# I2C_Step_12V_Ann.net
KiCad netlist of a schematic drawn in Altium Designer
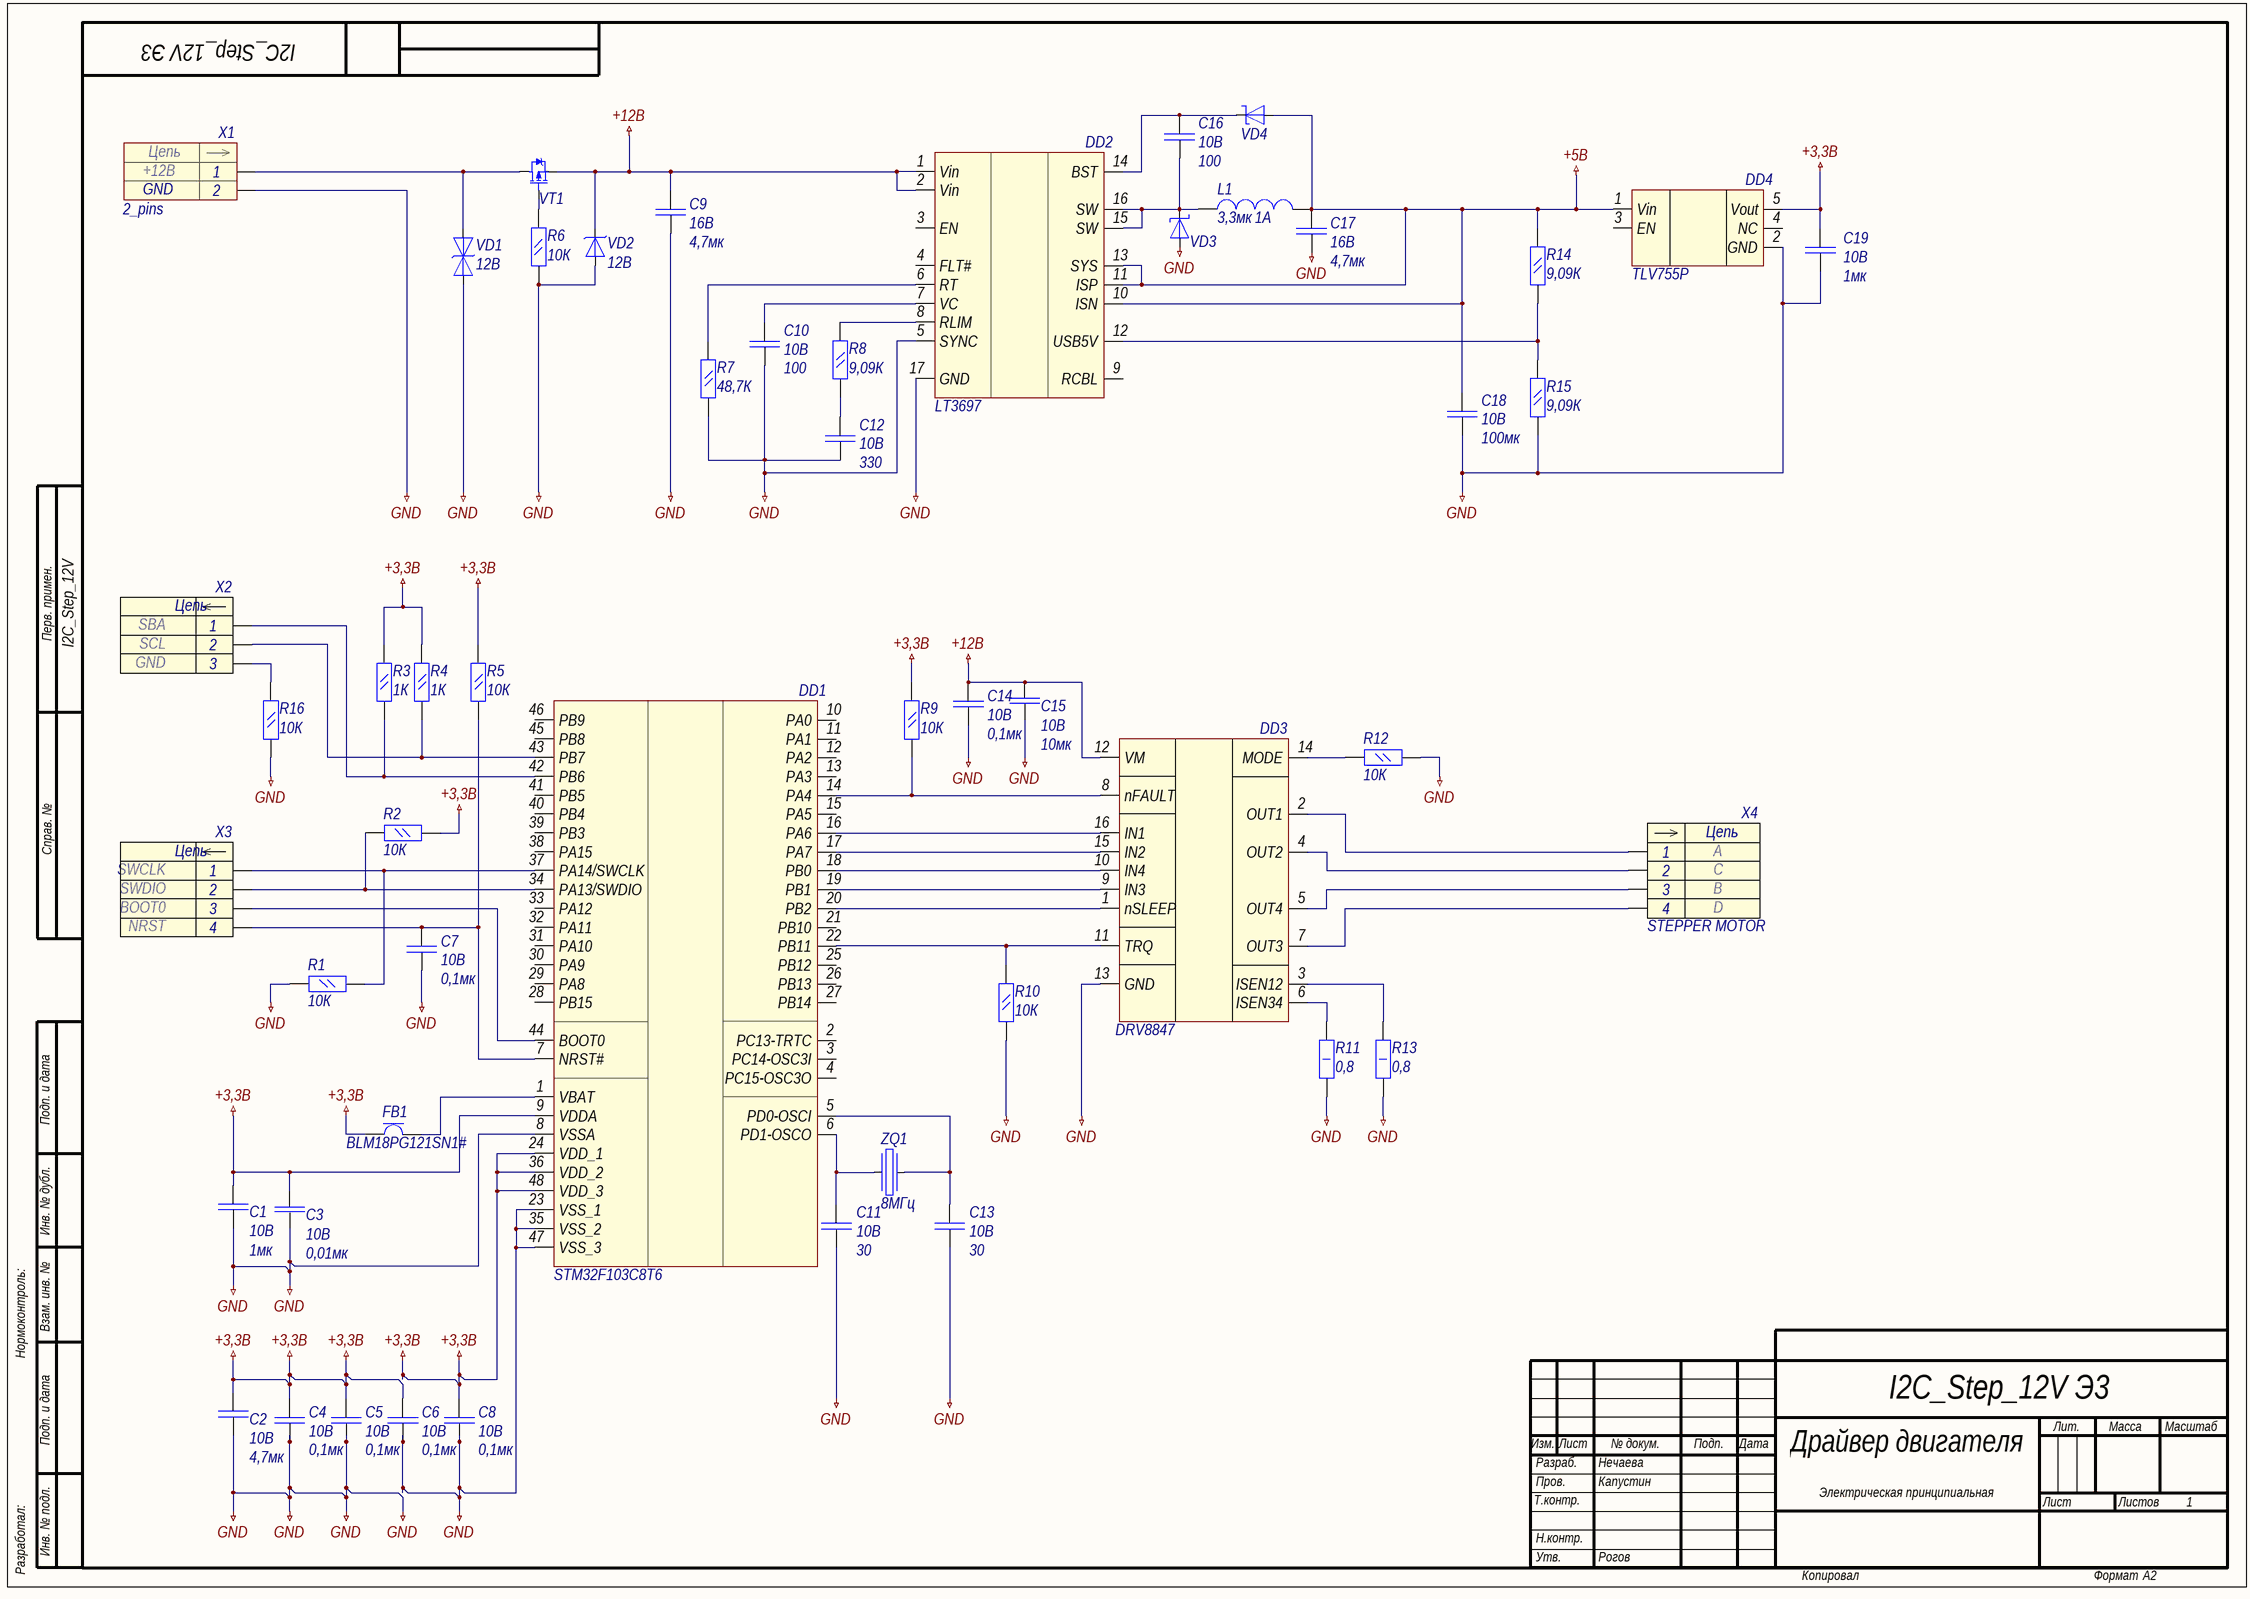
[diagram p0: I2C_Step_12V_Ann.SchDoc]

(export (version "E")
  (design (tool "Eeschema 10.0.6"))
  (components
    (comp (ref "C1")
      (value "Capacitor")
      (footprint "CH0201C")
      (fields (field (name "VOLTAGE") "10В") (field (name "CAPACITANCE") "1мк"))
      (libsource (lib "") (part "Capacitor_1"))
    )
    (comp (ref "C2")
      (value "Capacitor")
      (footprint "CH0402C")
      (fields (field (name "VOLTAGE") "10В") (field (name "CAPACITANCE") "4,7мк"))
      (libsource (lib "") (part "Capacitor_1"))
    )
    (comp (ref "C3")
      (value "Capacitor")
      (footprint "CH0402C")
      (fields (field (name "VOLTAGE") "10В") (field (name "CAPACITANCE") "0,01мк"))
      (libsource (lib "GOST_Capacitors") (part "Capacitor"))
    )
    (comp (ref "C4")
      (value "Capacitor")
      (footprint "CH0402C")
      (fields (field (name "VOLTAGE") "10В") (field (name "CAPACITANCE") "0,1мк"))
      (libsource (lib "") (part "Capacitor_1"))
    )
    (comp (ref "C5")
      (value "Capacitor")
      (footprint "CH0402C")
      (fields (field (name "VOLTAGE") "10В") (field (name "CAPACITANCE") "0,1мк"))
      (libsource (lib "") (part "Capacitor_1"))
    )
    (comp (ref "C6")
      (value "Capacitor")
      (footprint "CH0402C")
      (fields (field (name "VOLTAGE") "10В") (field (name "CAPACITANCE") "0,1мк"))
      (libsource (lib "") (part "Capacitor_1"))
    )
    (comp (ref "C7")
      (value "Capacitor")
      (footprint "CH0402C")
      (fields (field (name "VOLTAGE") "10В") (field (name "CAPACITANCE") "0,1мк"))
      (libsource (lib "") (part "Capacitor_1"))
    )
    (comp (ref "C8")
      (value "Capacitor")
      (footprint "CH0402C")
      (fields (field (name "VOLTAGE") "10В") (field (name "CAPACITANCE") "0,1мк"))
      (libsource (lib "") (part "Capacitor_1"))
    )
    (comp (ref "C9")
      (value "Capacitor")
      (footprint "CH0603C")
      (fields (field (name "VOLTAGE") "16В") (field (name "CAPACITANCE") "4,7мк"))
      (libsource (lib "") (part "Capacitor_1"))
    )
    (comp (ref "C10")
      (value "Capacitor")
      (footprint "CH0201C")
      (fields (field (name "VOLTAGE") "10В") (field (name "CAPACITANCE") "100"))
      (libsource (lib "") (part "Capacitor_1"))
    )
    (comp (ref "C11")
      (value "Capacitor")
      (footprint "CH0201C")
      (fields (field (name "VOLTAGE") "10В") (field (name "CAPACITANCE") "30"))
      (libsource (lib "") (part "Capacitor_1"))
    )
    (comp (ref "C12")
      (value "Capacitor")
      (footprint "CH0402C")
      (fields (field (name "VOLTAGE") "10В") (field (name "CAPACITANCE") "330"))
      (libsource (lib "") (part "Capacitor_1"))
    )
    (comp (ref "C13")
      (value "Capacitor")
      (footprint "CH0201C")
      (fields (field (name "VOLTAGE") "10В") (field (name "CAPACITANCE") "30"))
      (libsource (lib "") (part "Capacitor_1"))
    )
    (comp (ref "C14")
      (value "Capacitor")
      (footprint "CH0402C")
      (fields (field (name "VOLTAGE") "10В") (field (name "CAPACITANCE") "0,1мк"))
      (libsource (lib "") (part "Capacitor_1"))
    )
    (comp (ref "C15")
      (value "Capacitor")
      (footprint "CH0402C")
      (fields (field (name "VOLTAGE") "10В") (field (name "CAPACITANCE") "10мк"))
      (libsource (lib "GOST_Capacitors") (part "Capacitor"))
    )
    (comp (ref "C16")
      (value "Capacitor")
      (footprint "CH0201C")
      (fields (field (name "VOLTAGE") "10В") (field (name "CAPACITANCE") "100"))
      (libsource (lib "") (part "Capacitor_1"))
    )
    (comp (ref "C17")
      (value "Capacitor")
      (footprint "CH0603C")
      (fields (field (name "VOLTAGE") "16В") (field (name "CAPACITANCE") "4,7мк"))
      (libsource (lib "") (part "Capacitor_1"))
    )
    (comp (ref "C18")
      (value "Capacitor")
      (footprint "CH1206C")
      (fields (field (name "VOLTAGE") "10В") (field (name "CAPACITANCE") "100мк"))
      (libsource (lib "") (part "Capacitor_1"))
    )
    (comp (ref "C19")
      (value "Capacitor")
      (footprint "CH0201C")
      (fields (field (name "VOLTAGE") "10В") (field (name "CAPACITANCE") "1мк"))
      (libsource (lib "") (part "Capacitor_1"))
    )
    (comp (ref "DD1")
      (value "STM32F103C8T6")
      (footprint "STM32F103 48pins")
      (libsource (lib "GOST_lib_devices") (part "STM32"))
    )
    (comp (ref "DD2")
      (value "LT3697")
      (footprint "LT3697")
      (description "6~18 to 5")
      (libsource (lib "GOST_lib_devices") (part "LT3697"))
    )
    (comp (ref "DD3")
      (value "DRV8847")
      (footprint "DRV8847")
      (libsource (lib "GOST_lib_devices") (part "DRV8847"))
    )
    (comp (ref "DD4")
      (value "TLV755P")
      (footprint "SOT23-5")
      (libsource (lib "GOST_lib_devices") (part "LDO +3.3V"))
    )
    (comp (ref "FB1")
      (value "Ferrite bead")
      (footprint "CH0603L")
      (fields (field (name "MODEL") "BLM18PG121SN1#"))
      (libsource (lib "GOST_Inductors") (part "Ferrite bead"))
    )
    (comp (ref "L1")
      (value "*")
      (footprint "CH0805L")
      (fields (field (name "MAX CURRENT") "1А") (field (name "INDUCTANCE") "3,3мк"))
      (libsource (lib "GOST_Inductors") (part "Inductor"))
    )
    (comp (ref "R1")
      (value "Res_0.125")
      (footprint "CH0402R")
      (fields (field (name "IMPEDANCE") "10К"))
      (libsource (lib "GOST_Resistors") (part "Res_0.125"))
    )
    (comp (ref "R2")
      (value "Res_0.125")
      (footprint "CH0402R")
      (fields (field (name "IMPEDANCE") "10К"))
      (libsource (lib "GOST_Resistors") (part "Res_0.125"))
    )
    (comp (ref "R3")
      (value "Res_0.125")
      (footprint "CH0402R")
      (fields (field (name "IMPEDANCE") "1К"))
      (libsource (lib "GOST_Resistors") (part "Res_0.125"))
    )
    (comp (ref "R4")
      (value "Res_0.125")
      (footprint "CH0402R")
      (fields (field (name "IMPEDANCE") "1К"))
      (libsource (lib "GOST_Resistors") (part "Res_0.125"))
    )
    (comp (ref "R5")
      (value "Res_0.125")
      (footprint "CH0402R")
      (fields (field (name "IMPEDANCE") "10К"))
      (libsource (lib "GOST_Resistors") (part "Res_0.125"))
    )
    (comp (ref "R6")
      (value "Res_0.125")
      (footprint "CH0402R")
      (fields (field (name "IMPEDANCE") "10К"))
      (libsource (lib "GOST_Resistors") (part "Res_0.125"))
    )
    (comp (ref "R7")
      (value "Res_0.125")
      (footprint "CH0805R")
      (fields (field (name "IMPEDANCE") "48,7К"))
      (libsource (lib "GOST_Resistors") (part "Res_0.125"))
    )
    (comp (ref "R8")
      (value "Res_0.125")
      (footprint "CH0805R")
      (fields (field (name "IMPEDANCE") "9,09К"))
      (libsource (lib "GOST_Resistors") (part "Res_0.125"))
    )
    (comp (ref "R9")
      (value "Res_0.125")
      (footprint "CH0402R")
      (fields (field (name "IMPEDANCE") "10К"))
      (libsource (lib "GOST_Resistors") (part "Res_0.125"))
    )
    (comp (ref "R10")
      (value "Res_0.125")
      (footprint "CH0402R")
      (fields (field (name "IMPEDANCE") "10К"))
      (libsource (lib "GOST_Resistors") (part "Res_0.125"))
    )
    (comp (ref "R11")
      (value "Res_1")
      (footprint "CH2010R")
      (fields (field (name "POWER") "1Вт") (field (name "IMPEDANCE") "0,8"))
      (libsource (lib "GOST_Resistors") (part "Res_1"))
    )
    (comp (ref "R12")
      (value "Res_0.125")
      (footprint "CH0402R")
      (fields (field (name "IMPEDANCE") "10К"))
      (libsource (lib "GOST_Resistors") (part "Res_0.125"))
    )
    (comp (ref "R13")
      (value "Res_1")
      (footprint "CH2010R")
      (fields (field (name "POWER") "1Вт") (field (name "IMPEDANCE") "0,8"))
      (libsource (lib "GOST_Resistors") (part "Res_1"))
    )
    (comp (ref "R14")
      (value "Res_0.125")
      (footprint "CH0805R")
      (fields (field (name "IMPEDANCE") "9,09К"))
      (libsource (lib "GOST_Resistors") (part "Res_0.125"))
    )
    (comp (ref "R15")
      (value "Res_0.125")
      (footprint "CH0805R")
      (fields (field (name "IMPEDANCE") "9,09К"))
      (libsource (lib "GOST_Resistors") (part "Res_0.125"))
    )
    (comp (ref "R16")
      (value "Res_0.125")
      (footprint "CH0402R")
      (fields (field (name "IMPEDANCE") "10К"))
      (libsource (lib "GOST_Resistors") (part "Res_0.125"))
    )
    (comp (ref "VD1")
      (value "TVS-diod_simmetrical")
      (footprint "CH0201L")
      (fields (field (name "MANUFACTURER") "Littelfuse") (field (name "CLAMPING VOLTAGE") "12В"))
      (libsource (lib "GOST_Diodes") (part "TVS-diod_simmetrical"))
    )
    (comp (ref "VD2")
      (value "TVS-diod_directed")
      (footprint "DO214AA")
      (fields (field (name "MANUFACTURER") "Bourns") (field (name "CLAMPING_VOLTAGE") "12В"))
      (libsource (lib "GOST_Diodes") (part "TVS-diod_directed"))
    )
    (comp (ref "VD3")
      (value "Diod Schottky")
      (footprint "DO214AA")
      (fields (field (name "MANUFACTURER") "Rectron"))
      (libsource (lib "GOST_Diodes") (part "Diod Schottky"))
    )
    (comp (ref "VD4")
      (value "Diod Schottky")
      (footprint "SOT23_132")
      (fields (field (name "MANUFACTURER") "Toshiba"))
      (libsource (lib "GOST_Diodes") (part "Diod Schottky"))
    )
    (comp (ref "VT1")
      (value "*")
      (footprint "SOT23_132")
      (libsource (lib "GOST_Transistors") (part "P-Channel"))
    )
    (comp (ref "X1")
      (value "2_pins")
      (footprint "CON: 163-179PH-EX")
      (fields (field (name "VCC") "+12В"))
      (libsource (lib "GOST_lib_connectors") (part "2_pins"))
    )
    (comp (ref "X2")
      (value "3_pins")
      (footprint "CON: PBS-3")
      (fields (field (name "2") "SCL") (field (name "3") "GND") (field (name "1") "SBA"))
      (libsource (lib "GOST_lib_connectors") (part "3_pins"))
    )
    (comp (ref "X3")
      (value "4_pins")
      (footprint "CON: CWF-4R")
      (fields
        (field (name "2") "SWDIO")
        (field (name "3") "BOOT0")
        (field (name "1") "SWCLK")
        (field (name "4") "NRST")
      )
      (libsource (lib "") (part "4_pins_1"))
    )
    (comp (ref "X4")
      (value "STEPPER MOTOR")
      (footprint "CON: CWF-4R")
      (description "Bipolar Stepper Motor 200 Step 0.35A 12VDC")
      (fields (field (name "2") "C") (field (name "3") "B") (field (name "1") "A") (field (name "4") "D"))
      (libsource (lib "GOST_lib_connectors") (part "4_pins"))
    )
    (comp (ref "ZQ1")
      (value "Oscillator")
      (footprint "OSC: 5032")
      (fields (field (name "FREQ") "8МГц"))
      (libsource (lib "GOST_Miscelanuious") (part "Oscillator"))
    )
  )
  (nets
    (net (code "1") (name "+3,3В") (class "Default")
      (node (ref "C1") (pin "2") (pinfunction "C1-_2") (pintype "power_in"))
      (node (ref "C19") (pin "1") (pinfunction "C1+_1") (pintype "power_in"))
      (node (ref "C2") (pin "2") (pinfunction "C1-_2") (pintype "power_in"))
      (node (ref "C3") (pin "1") (pinfunction "С+_1") (pintype "power_in"))
      (node (ref "C4") (pin "1") (pinfunction "C1+_1") (pintype "power_in"))
      (node (ref "C5") (pin "1") (pinfunction "C1+_1") (pintype "power_in"))
      (node (ref "C6") (pin "1") (pinfunction "C1+_1") (pintype "power_in"))
      (node (ref "C8") (pin "1") (pinfunction "C1+_1") (pintype "power_in"))
      (node (ref "DD1") (pin "24") (pinfunction "VDD_1_24") (pintype "passive"))
      (node (ref "DD1") (pin "36") (pinfunction "VDD_2_36") (pintype "passive"))
      (node (ref "DD1") (pin "48") (pinfunction "VDD_3_48") (pintype "passive"))
      (node (ref "DD1") (pin "9") (pinfunction "VDDA_9") (pintype "passive"))
      (node (ref "DD4") (pin "5") (pinfunction "Vout_5") (pintype "power_in"))
      (node (ref "FB1") (pin "1") (pintype "power_in"))
      (node (ref "R2") (pin "1") (pinfunction "C1-_1") (pintype "power_in"))
      (node (ref "R3") (pin "1") (pinfunction "C1-_1") (pintype "power_in"))
      (node (ref "R4") (pin "1") (pinfunction "C1-_1") (pintype "power_in"))
      (node (ref "R5") (pin "1") (pinfunction "C1-_1") (pintype "power_in"))
      (node (ref "R9") (pin "1") (pinfunction "C1-_1") (pintype "power_in"))
    )
    (net (code "2") (name "+5В") (class "Default")
      (node (ref "C17") (pin "1") (pinfunction "C1+_1") (pintype "power_in"))
      (node (ref "C18") (pin "1") (pinfunction "C1+_1") (pintype "power_in"))
      (node (ref "DD2") (pin "10") (pinfunction "ISN_10") (pintype "power_in"))
      (node (ref "DD2") (pin "11") (pinfunction "ISP_11") (pintype "power_in"))
      (node (ref "DD2") (pin "13") (pinfunction "SYS_13") (pintype "power_in"))
      (node (ref "DD4") (pin "1") (pinfunction "Vin_1") (pintype "power_in"))
      (node (ref "L1") (pin "2") (pinfunction "14_2") (pintype "power_in"))
      (node (ref "R14") (pin "1") (pinfunction "C1-_1") (pintype "power_in"))
      (node (ref "VD4") (pin "1") (pinfunction "1_1") (pintype "passive"))
    )
    (net (code "3") (name "+12В") (class "Default")
      (node (ref "C14") (pin "1") (pinfunction "C1+_1") (pintype "power_in"))
      (node (ref "C15") (pin "1") (pinfunction "С+_1") (pintype "power_in"))
      (node (ref "C9") (pin "1") (pinfunction "C1+_1") (pintype "power_in"))
      (node (ref "DD2") (pin "1") (pinfunction "Vin_1") (pintype "power_in"))
      (node (ref "DD2") (pin "2") (pinfunction "Vin_2") (pintype "power_in"))
      (node (ref "DD3") (pin "12") (pinfunction "VM_12") (pintype "power_in"))
      (node (ref "VD2") (pin "2") (pinfunction "C_2") (pintype "passive"))
      (node (ref "VT1") (pin "3") (pinfunction "S_3") (pintype "passive"))
    )
    (net (code "4") (name "GND") (class "Default")
      (node (ref "C1") (pin "1") (pinfunction "C1+_1") (pintype "power_in"))
      (node (ref "C10") (pin "2") (pinfunction "C1-_2") (pintype "power_in"))
      (node (ref "C11") (pin "2") (pinfunction "C1-_2") (pintype "power_in"))
      (node (ref "C12") (pin "2") (pinfunction "C1-_2") (pintype "power_in"))
      (node (ref "C13") (pin "2") (pinfunction "C1-_2") (pintype "power_in"))
      (node (ref "C14") (pin "2") (pinfunction "C1-_2") (pintype "power_in"))
      (node (ref "C15") (pin "2") (pinfunction "С-_2") (pintype "power_in"))
      (node (ref "C17") (pin "2") (pinfunction "C1-_2") (pintype "power_in"))
      (node (ref "C18") (pin "2") (pinfunction "C1-_2") (pintype "power_in"))
      (node (ref "C19") (pin "2") (pinfunction "C1-_2") (pintype "power_in"))
      (node (ref "C2") (pin "1") (pinfunction "C1+_1") (pintype "power_in"))
      (node (ref "C3") (pin "2") (pinfunction "С-_2") (pintype "power_in"))
      (node (ref "C4") (pin "2") (pinfunction "C1-_2") (pintype "power_in"))
      (node (ref "C5") (pin "2") (pinfunction "C1-_2") (pintype "power_in"))
      (node (ref "C6") (pin "2") (pinfunction "C1-_2") (pintype "power_in"))
      (node (ref "C7") (pin "2") (pinfunction "C1-_2") (pintype "power_in"))
      (node (ref "C8") (pin "2") (pinfunction "C1-_2") (pintype "power_in"))
      (node (ref "C9") (pin "2") (pinfunction "C1-_2") (pintype "power_in"))
      (node (ref "DD1") (pin "23") (pinfunction "VSS_1_23") (pintype "passive"))
      (node (ref "DD1") (pin "35") (pinfunction "VSS_2_35") (pintype "passive"))
      (node (ref "DD1") (pin "47") (pinfunction "VSS_3_47") (pintype "passive"))
      (node (ref "DD1") (pin "8") (pinfunction "VSSA_8") (pintype "passive"))
      (node (ref "DD2") (pin "17") (pinfunction "GND_17") (pintype "power_in"))
      (node (ref "DD2") (pin "5") (pinfunction "SYNC_5") (pintype "power_in"))
      (node (ref "DD3") (pin "13") (pinfunction "GND_13") (pintype "power_in"))
      (node (ref "DD4") (pin "2") (pinfunction "GND_2") (pintype "power_in"))
      (node (ref "R1") (pin "2") (pinfunction "C1-_2") (pintype "power_in"))
      (node (ref "R10") (pin "2") (pinfunction "C1-_2") (pintype "power_in"))
      (node (ref "R11") (pin "1") (pinfunction "*_1") (pintype "power_in"))
      (node (ref "R12") (pin "1") (pinfunction "C1-_1") (pintype "power_in"))
      (node (ref "R13") (pin "1") (pinfunction "*_1") (pintype "power_in"))
      (node (ref "R15") (pin "2") (pinfunction "C1-_2") (pintype "power_in"))
      (node (ref "R16") (pin "2") (pinfunction "C1-_2") (pintype "power_in"))
      (node (ref "R6") (pin "1") (pinfunction "C1-_1") (pintype "power_in"))
      (node (ref "R7") (pin "2") (pinfunction "C1-_2") (pintype "power_in"))
      (node (ref "VD1") (pin "1") (pinfunction "A_1") (pintype "passive"))
      (node (ref "VD2") (pin "1") (pinfunction "A_1") (pintype "passive"))
      (node (ref "VD3") (pin "1") (pinfunction "1_1") (pintype "passive"))
      (node (ref "X1") (pin "2") (pinfunction "2_2") (pintype "passive"))
    )
    (net (code "5") (name "Net-(C7-C1+)") (class "Default")
      (node (ref "C7") (pin "1") (pinfunction "C1+_1") (pintype "power_in"))
      (node (ref "DD1") (pin "7") (pinfunction "NRST#_7") (pintype "passive"))
      (node (ref "R5") (pin "2") (pinfunction "C1-_2") (pintype "power_in"))
      (node (ref "X3") (pin "4") (pinfunction "4_4") (pintype "passive"))
    )
    (net (code "6") (name "Net-(C10-C1+)") (class "Default")
      (node (ref "C10") (pin "1") (pinfunction "C1+_1") (pintype "power_in"))
      (node (ref "DD2") (pin "7") (pinfunction "VC_7") (pintype "power_in"))
    )
    (net (code "7") (name "Net-(C11-C1+)") (class "Default")
      (node (ref "C11") (pin "1") (pinfunction "C1+_1") (pintype "power_in"))
      (node (ref "DD1") (pin "6") (pinfunction "PD1-OSCO_6") (pintype "passive"))
      (node (ref "ZQ1") (pin "1") (pintype "passive"))
    )
    (net (code "8") (name "Net-(C12-C1+)") (class "Default")
      (node (ref "C12") (pin "1") (pinfunction "C1+_1") (pintype "power_in"))
      (node (ref "R8") (pin "2") (pinfunction "C1-_2") (pintype "power_in"))
    )
    (net (code "9") (name "Net-(C13-C1+)") (class "Default")
      (node (ref "C13") (pin "1") (pinfunction "C1+_1") (pintype "power_in"))
      (node (ref "DD1") (pin "5") (pinfunction "PD0-OSCI_5") (pintype "passive"))
      (node (ref "ZQ1") (pin "3") (pintype "passive"))
    )
    (net (code "10") (name "Net-(C16-C1+)") (class "Default")
      (node (ref "C16") (pin "1") (pinfunction "C1+_1") (pintype "power_in"))
      (node (ref "DD2") (pin "14") (pinfunction "BST_14") (pintype "power_in"))
      (node (ref "VD4") (pin "2") (pinfunction "2_2") (pintype "passive"))
    )
    (net (code "11") (name "Net-(C16-C1-)") (class "Default")
      (node (ref "C16") (pin "2") (pinfunction "C1-_2") (pintype "power_in"))
      (node (ref "DD2") (pin "15") (pinfunction "SW_15") (pintype "power_in"))
      (node (ref "DD2") (pin "16") (pinfunction "SW_16") (pintype "power_in"))
      (node (ref "L1") (pin "1") (pinfunction "C1-_1") (pintype "power_in"))
      (node (ref "VD3") (pin "2") (pinfunction "2_2") (pintype "passive"))
    )
    (net (code "12") (name "Net-(DD1-BOOT0)") (class "Default")
      (node (ref "DD1") (pin "44") (pinfunction "BOOT0_44") (pintype "passive"))
      (node (ref "X3") (pin "3") (pinfunction "3_3") (pintype "passive"))
    )
    (net (code "13") (name "Net-(DD1-PA4)") (class "Default")
      (node (ref "DD1") (pin "14") (pinfunction "PA4_14") (pintype "passive"))
      (node (ref "DD3") (pin "8") (pinfunction "nFAULT_8") (pintype "power_in"))
      (node (ref "R9") (pin "2") (pinfunction "C1-_2") (pintype "power_in"))
    )
    (net (code "14") (name "Net-(DD1-PA6)") (class "Default")
      (node (ref "DD1") (pin "16") (pinfunction "PA6_16") (pintype "passive"))
      (node (ref "DD3") (pin "16") (pinfunction "IN1_16") (pintype "power_in"))
    )
    (net (code "15") (name "Net-(DD1-PA7)") (class "Default")
      (node (ref "DD1") (pin "17") (pinfunction "PA7_17") (pintype "passive"))
      (node (ref "DD3") (pin "15") (pinfunction "IN2_15") (pintype "power_in"))
    )
    (net (code "16") (name "Net-(DD1-PA13{slash}SWDIO)") (class "Default")
      (node (ref "DD1") (pin "34") (pinfunction "PA13/SWDIO_34") (pintype "passive"))
      (node (ref "R2") (pin "2") (pinfunction "C1-_2") (pintype "power_in"))
      (node (ref "X3") (pin "2") (pinfunction "2_2") (pintype "passive"))
    )
    (net (code "17") (name "Net-(DD1-PA14{slash}SWCLK)") (class "Default")
      (node (ref "DD1") (pin "37") (pinfunction "PA14/SWCLK_37") (pintype "passive"))
      (node (ref "R1") (pin "1") (pinfunction "C1-_1") (pintype "power_in"))
      (node (ref "X3") (pin "1") (pinfunction "1_1") (pintype "passive"))
    )
    (net (code "18") (name "Net-(DD1-PB0)") (class "Default")
      (node (ref "DD1") (pin "18") (pinfunction "PB0_18") (pintype "passive"))
      (node (ref "DD3") (pin "10") (pinfunction "IN4_10") (pintype "power_in"))
    )
    (net (code "19") (name "Net-(DD1-PB1)") (class "Default")
      (node (ref "DD1") (pin "19") (pinfunction "PB1_19") (pintype "passive"))
      (node (ref "DD3") (pin "9") (pinfunction "IN3_9") (pintype "power_in"))
    )
    (net (code "20") (name "Net-(DD1-PB2)") (class "Default")
      (node (ref "DD1") (pin "20") (pinfunction "PB2_20") (pintype "passive"))
      (node (ref "DD3") (pin "1") (pinfunction "nSLEEP_1") (pintype "power_in"))
    )
    (net (code "21") (name "Net-(DD1-PB6)") (class "Default")
      (node (ref "DD1") (pin "42") (pinfunction "PB6_42") (pintype "passive"))
      (node (ref "R3") (pin "2") (pinfunction "C1-_2") (pintype "power_in"))
      (node (ref "X2") (pin "1") (pinfunction "1_1") (pintype "passive"))
    )
    (net (code "22") (name "Net-(DD1-PB7)") (class "Default")
      (node (ref "DD1") (pin "43") (pinfunction "PB7_43") (pintype "passive"))
      (node (ref "R4") (pin "2") (pinfunction "C1-_2") (pintype "power_in"))
      (node (ref "X2") (pin "2") (pinfunction "2_2") (pintype "passive"))
    )
    (net (code "23") (name "Net-(DD1-PB11)") (class "Default")
      (node (ref "DD1") (pin "22") (pinfunction "PB11_22") (pintype "passive"))
      (node (ref "DD3") (pin "11") (pinfunction "TRQ_11") (pintype "power_in"))
      (node (ref "R10") (pin "1") (pinfunction "C1-_1") (pintype "power_in"))
    )
    (net (code "24") (name "Net-(DD1-VBAT)") (class "Default")
      (node (ref "DD1") (pin "1") (pinfunction "VBAT_1") (pintype "passive"))
      (node (ref "FB1") (pin "2") (pintype "power_in"))
    )
    (net (code "25") (name "Net-(DD2-RLIM)") (class "Default")
      (node (ref "DD2") (pin "8") (pinfunction "RLIM_8") (pintype "power_in"))
      (node (ref "R8") (pin "1") (pinfunction "C1-_1") (pintype "power_in"))
    )
    (net (code "26") (name "Net-(DD2-RT)") (class "Default")
      (node (ref "DD2") (pin "6") (pinfunction "RT_6") (pintype "power_in"))
      (node (ref "R7") (pin "1") (pinfunction "C1-_1") (pintype "power_in"))
    )
    (net (code "27") (name "Net-(DD2-USB5V)") (class "Default")
      (node (ref "DD2") (pin "12") (pinfunction "USB5V_12") (pintype "power_in"))
      (node (ref "R14") (pin "2") (pinfunction "C1-_2") (pintype "power_in"))
      (node (ref "R15") (pin "1") (pinfunction "C1-_1") (pintype "power_in"))
    )
    (net (code "28") (name "Net-(DD3-ISEN12)") (class "Default")
      (node (ref "DD3") (pin "3") (pinfunction "ISEN12_3") (pintype "power_in"))
      (node (ref "R13") (pin "2") (pinfunction "*_2") (pintype "power_in"))
    )
    (net (code "29") (name "Net-(DD3-ISEN34)") (class "Default")
      (node (ref "DD3") (pin "6") (pinfunction "ISEN34_6") (pintype "power_in"))
      (node (ref "R11") (pin "2") (pinfunction "*_2") (pintype "power_in"))
    )
    (net (code "30") (name "Net-(DD3-MODE)") (class "Default")
      (node (ref "DD3") (pin "14") (pinfunction "MODE_14") (pintype "power_in"))
      (node (ref "R12") (pin "2") (pinfunction "C1-_2") (pintype "power_in"))
    )
    (net (code "31") (name "Net-(DD3-OUT1)") (class "Default")
      (node (ref "DD3") (pin "2") (pinfunction "OUT1_2") (pintype "power_in"))
      (node (ref "X4") (pin "1") (pinfunction "1_1") (pintype "passive"))
    )
    (net (code "32") (name "Net-(DD3-OUT2)") (class "Default")
      (node (ref "DD3") (pin "4") (pinfunction "OUT2_4") (pintype "power_in"))
      (node (ref "X4") (pin "2") (pinfunction "2_2") (pintype "passive"))
    )
    (net (code "33") (name "Net-(DD3-OUT3)") (class "Default")
      (node (ref "DD3") (pin "7") (pinfunction "OUT3_7") (pintype "power_in"))
      (node (ref "X4") (pin "4") (pinfunction "4_4") (pintype "passive"))
    )
    (net (code "34") (name "Net-(DD3-OUT4)") (class "Default")
      (node (ref "DD3") (pin "5") (pinfunction "OUT4_5") (pintype "power_in"))
      (node (ref "X4") (pin "3") (pinfunction "3_3") (pintype "passive"))
    )
    (net (code "35") (name "Net-(R16-C1--Pad1)") (class "Default")
      (node (ref "R16") (pin "1") (pinfunction "C1-_1") (pintype "power_in"))
      (node (ref "X2") (pin "3") (pinfunction "3_3") (pintype "passive"))
    )
    (net (code "36") (name "Net-(VD1-C)") (class "Default")
      (node (ref "VD1") (pin "2") (pinfunction "C_2") (pintype "passive"))
      (node (ref "VT1") (pin "2") (pinfunction "D_2") (pintype "passive"))
      (node (ref "X1") (pin "1") (pinfunction "1_1") (pintype "passive"))
    )
    (net (code "37") (name "Net-(VT1-G)") (class "Default")
      (node (ref "R6") (pin "2") (pinfunction "C1-_2") (pintype "power_in"))
      (node (ref "VT1") (pin "1") (pinfunction "G_1") (pintype "passive"))
    )
    (net (code "38") (name "unconnected-(DD1-PA0-Pad10)") (class "Default")
      (node (ref "DD1") (pin "10") (pinfunction "PA0_10") (pintype "passive"))
    )
    (net (code "39") (name "unconnected-(DD1-PA1-Pad11)") (class "Default")
      (node (ref "DD1") (pin "11") (pinfunction "PA1_11") (pintype "passive"))
    )
    (net (code "40") (name "unconnected-(DD1-PA2-Pad12)") (class "Default")
      (node (ref "DD1") (pin "12") (pinfunction "PA2_12") (pintype "passive"))
    )
    (net (code "41") (name "unconnected-(DD1-PA3-Pad13)") (class "Default")
      (node (ref "DD1") (pin "13") (pinfunction "PA3_13") (pintype "passive"))
    )
    (net (code "42") (name "unconnected-(DD1-PA5-Pad15)") (class "Default")
      (node (ref "DD1") (pin "15") (pinfunction "PA5_15") (pintype "passive"))
    )
    (net (code "43") (name "unconnected-(DD1-PA8-Pad29)") (class "Default")
      (node (ref "DD1") (pin "29") (pinfunction "PA8_29") (pintype "passive"))
    )
    (net (code "44") (name "unconnected-(DD1-PA9-Pad30)") (class "Default")
      (node (ref "DD1") (pin "30") (pinfunction "PA9_30") (pintype "passive"))
    )
    (net (code "45") (name "unconnected-(DD1-PA10-Pad31)") (class "Default")
      (node (ref "DD1") (pin "31") (pinfunction "PA10_31") (pintype "passive"))
    )
    (net (code "46") (name "unconnected-(DD1-PA11-Pad32)") (class "Default")
      (node (ref "DD1") (pin "32") (pinfunction "PA11_32") (pintype "passive"))
    )
    (net (code "47") (name "unconnected-(DD1-PA12-Pad33)") (class "Default")
      (node (ref "DD1") (pin "33") (pinfunction "PA12_33") (pintype "passive"))
    )
    (net (code "48") (name "unconnected-(DD1-PA15-Pad38)") (class "Default")
      (node (ref "DD1") (pin "38") (pinfunction "PA15_38") (pintype "passive"))
    )
    (net (code "49") (name "unconnected-(DD1-PB3-Pad39)") (class "Default")
      (node (ref "DD1") (pin "39") (pinfunction "PB3_39") (pintype "passive"))
    )
    (net (code "50") (name "unconnected-(DD1-PB4-Pad40)") (class "Default")
      (node (ref "DD1") (pin "40") (pinfunction "PB4_40") (pintype "passive"))
    )
    (net (code "51") (name "unconnected-(DD1-PB5-Pad41)") (class "Default")
      (node (ref "DD1") (pin "41") (pinfunction "PB5_41") (pintype "passive"))
    )
    (net (code "52") (name "unconnected-(DD1-PB8-Pad45)") (class "Default")
      (node (ref "DD1") (pin "45") (pinfunction "PB8_45") (pintype "passive"))
    )
    (net (code "53") (name "unconnected-(DD1-PB9-Pad46)") (class "Default")
      (node (ref "DD1") (pin "46") (pinfunction "PB9_46") (pintype "passive"))
    )
    (net (code "54") (name "unconnected-(DD1-PB10-Pad21)") (class "Default")
      (node (ref "DD1") (pin "21") (pinfunction "PB10_21") (pintype "passive"))
    )
    (net (code "55") (name "unconnected-(DD1-PB12-Pad25)") (class "Default")
      (node (ref "DD1") (pin "25") (pinfunction "PB12_25") (pintype "passive"))
    )
    (net (code "56") (name "unconnected-(DD1-PB13-Pad26)") (class "Default")
      (node (ref "DD1") (pin "26") (pinfunction "PB13_26") (pintype "passive"))
    )
    (net (code "57") (name "unconnected-(DD1-PB14-Pad27)") (class "Default")
      (node (ref "DD1") (pin "27") (pinfunction "PB14_27") (pintype "passive"))
    )
    (net (code "58") (name "unconnected-(DD1-PB15-Pad28)") (class "Default")
      (node (ref "DD1") (pin "28") (pinfunction "PB15_28") (pintype "passive"))
    )
    (net (code "59") (name "unconnected-(DD1-PC13-TRTC-Pad2)") (class "Default")
      (node (ref "DD1") (pin "2") (pinfunction "PC13-TRTC_2") (pintype "passive"))
    )
    (net (code "60") (name "unconnected-(DD1-PC14-OSC3I-Pad3)") (class "Default")
      (node (ref "DD1") (pin "3") (pinfunction "PC14-OSC3I_3") (pintype "passive"))
    )
    (net (code "61") (name "unconnected-(DD1-PC15-OSC3O-Pad4)") (class "Default")
      (node (ref "DD1") (pin "4") (pinfunction "PC15-OSC3O_4") (pintype "passive"))
    )
    (net (code "62") (name "unconnected-(DD2-EN-Pad3)") (class "Default")
      (node (ref "DD2") (pin "3") (pinfunction "EN_3") (pintype "power_in"))
    )
    (net (code "63") (name "unconnected-(DD2-FLT#-Pad4)") (class "Default")
      (node (ref "DD2") (pin "4") (pinfunction "FLT#_4") (pintype "power_in"))
    )
    (net (code "64") (name "unconnected-(DD2-RCBL-Pad9)") (class "Default")
      (node (ref "DD2") (pin "9") (pinfunction "RCBL_9") (pintype "power_in"))
    )
    (net (code "65") (name "unconnected-(DD4-EN-Pad3)") (class "Default")
      (node (ref "DD4") (pin "3") (pinfunction "EN_3") (pintype "power_in"))
    )
    (net (code "66") (name "unconnected-(DD4-NC-Pad4)") (class "Default")
      (node (ref "DD4") (pin "4") (pinfunction "NC_4") (pintype "power_in"))
    )
  )
)
